# H19R1_Frontend_1.net
KiCad netlist of a schematic drawn in Altium Designer
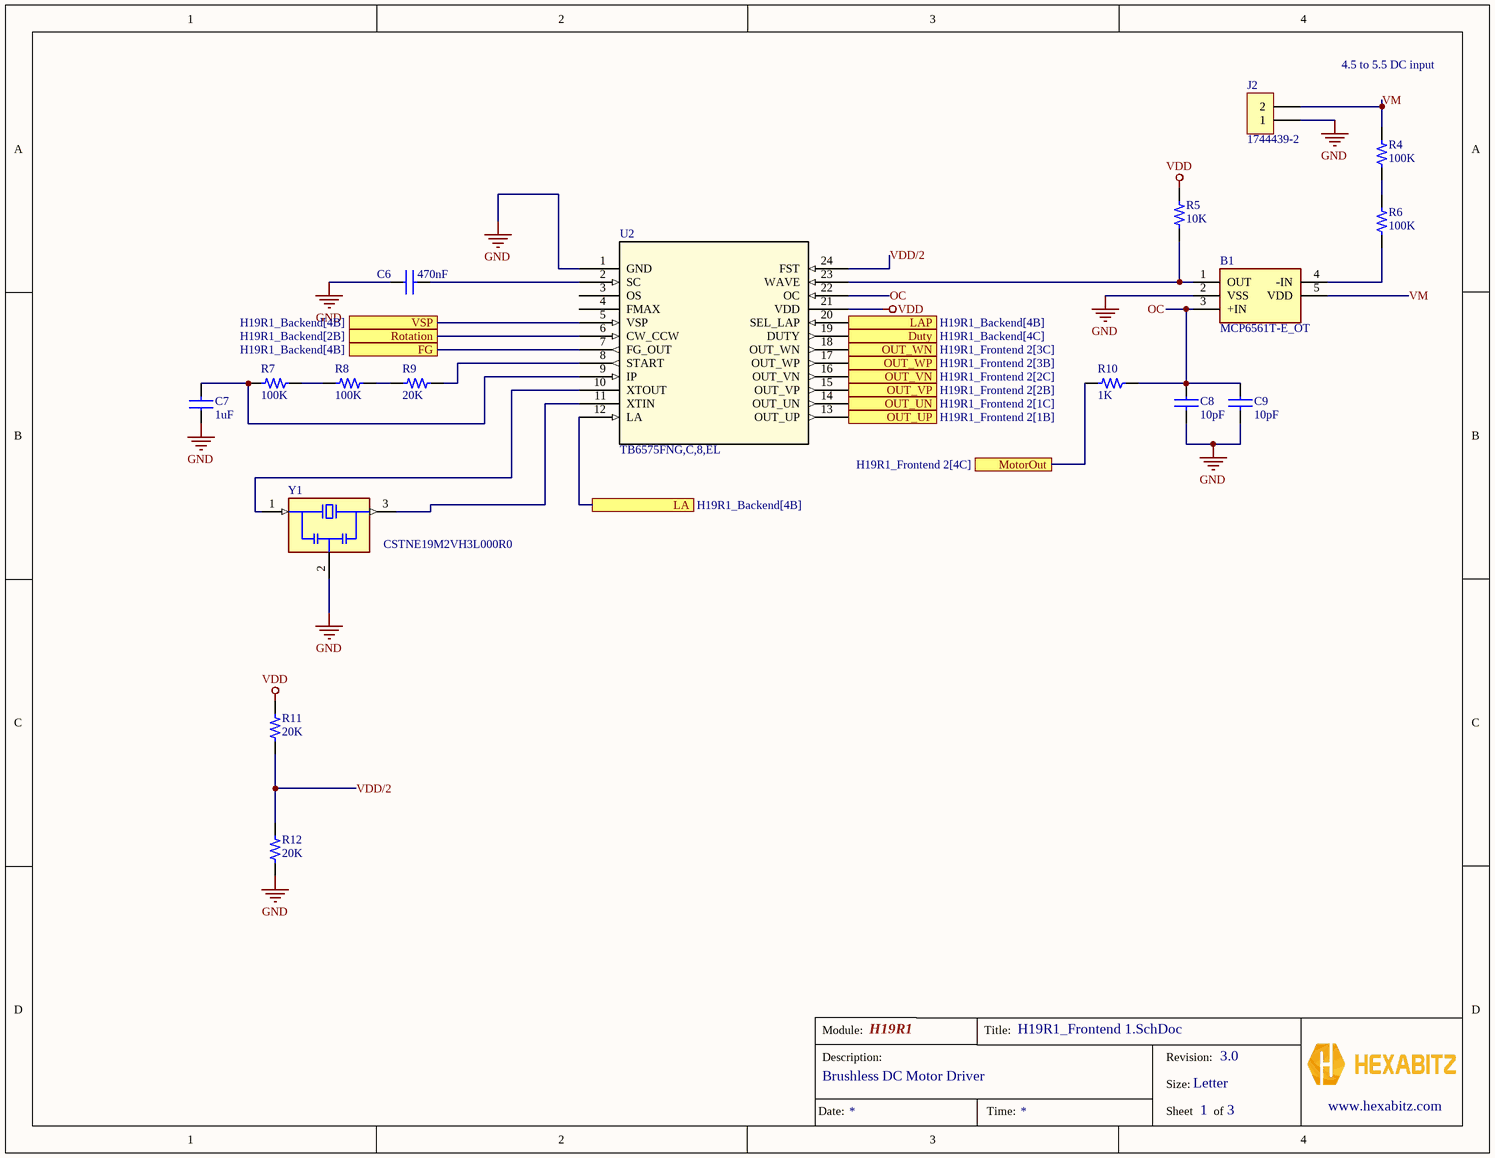
[diagram p0: H19R1_Frontend 1.SchDoc]

(export (version "E")
  (design (tool "Eeschema 10.0.6"))
  (components
    (comp (ref "B1")
      (value "MCP6561T-E_OT")
      (footprint "SOT95P270X145-5N")
      (description "Single 1.8V Push/Pull Comparator, E temp")
      (fields (field (name "MANUFACTURER_PART_NUMBER") "MCP6561T-E/OT"))
      (libsource (lib "MCP6561T-E_OT") (part "MCP6561T-E_OT"))
    )
    (comp (ref "C6")
      (value "470nF")
      (footprint "C0402")
      (description "Multilayer Ceramic Capacitor, 0.47 uF, 16 V, ± 10%, X7S, 0402 [1005 Metric]")
      (fields
        (field (name "MANUFACTURER") "TDK")
        (field (name "MANUFACTURER PART NUMBER") "C1005X7S1C474K050BC")
      )
      (libsource (lib "Passive") (part "C1005X7S1C474K050BC"))
    )
    (comp (ref "C7")
      (value "1uF")
      (footprint "C0402")
      (description "Multilayer Ceramic Capacitor, 1 Uf, 25 V, ½ 10%, X5R, 0402 [1005 Metric]")
      (fields
        (field (name "MANUFACTURER") "Samsung")
        (field (name "MANUFACTURER PART NUMBER") "CL05A105KA5NQNC")
      )
      (libsource (lib "Passive") (part "CL05A105KA5NQNC"))
    )
    (comp (ref "C8")
      (value "10pF")
      (footprint "C0402")
      (description "0402 10 pF 50 V ±5 % Tolerance NP0 SMT Multilayer Ceramic Capacitor")
      (fields
        (field (name "MANUFACTURER") "Yageo")
        (field (name "MANUFACTURER PART NUMBER") "CC0402JRNPO9BN100")
      )
      (libsource (lib "Passive") (part "CC0402JRNPO9BN100"))
    )
    (comp (ref "C9")
      (value "10pF")
      (footprint "C0402")
      (description "0402 10 pF 50 V ±5 % Tolerance NP0 SMT Multilayer Ceramic Capacitor")
      (fields
        (field (name "MANUFACTURER") "Yageo")
        (field (name "MANUFACTURER PART NUMBER") "CC0402JRNPO9BN100")
      )
      (libsource (lib "Passive") (part "CC0402JRNPO9BN100"))
    )
    (comp (ref "J2")
      (value "1744439-2")
      (footprint "17444392")
      (description "Conn Shrouded Header HDR 2 POS 2.5mm Crimp ST Cable Mount Bag/Box")
      (fields
        (field (name "MANUFACTURER") "TE Connectivity AMP")
        (field (name "MANUFACTURER PART NUMBER") "1744439-2")
      )
      (libsource (lib "Connectors") (part "1744439-2"))
    )
    (comp (ref "R4")
      (value "100K")
      (footprint "R0402_3")
      (description "Res Thick Film 0402 100K Ohm 1% 1/10W ±100ppm/°C Molded SMD Punched Carrier T/R")
      (fields
        (field (name "MANUFACTURER") "Panasonic")
        (field (name "MANUFACTURER PART NUMBER") "ERJ-2RKF1003X")
      )
      (libsource (lib "") (part "ERJ-2RKF1003X_1"))
    )
    (comp (ref "R5")
      (value "10K")
      (footprint "R0402_3")
      (description "SMD Chip Resistor, 10 Kohm, ½ 1%, 62.5 Mw, 0402 [1005 Metric], Thick Film, General Purpose")
      (fields
        (field (name "MANUFACTURER") "Yageo")
        (field (name "MANUFACTURER PART NUMBER") "RC0402FR-0710KL")
      )
      (libsource (lib "Passive") (part "RC0402FR-0710KL"))
    )
    (comp (ref "R6")
      (value "100K")
      (footprint "R0402_3")
      (description "Res Thick Film 0402 100K Ohm 1% 1/10W ±100ppm/°C Molded SMD Punched Carrier T/R")
      (fields
        (field (name "MANUFACTURER") "Panasonic")
        (field (name "MANUFACTURER PART NUMBER") "ERJ-2RKF1003X")
      )
      (libsource (lib "") (part "ERJ-2RKF1003X_1"))
    )
    (comp (ref "R7")
      (value "100K")
      (footprint "R0402_3")
      (description "Res Thick Film 0402 100K Ohm 1% 1/10W ±100ppm/°C Molded SMD Punched Carrier T/R")
      (fields
        (field (name "MANUFACTURER") "Panasonic")
        (field (name "MANUFACTURER PART NUMBER") "ERJ-2RKF1003X")
      )
      (libsource (lib "Passive") (part "ERJ-2RKF1003X"))
    )
    (comp (ref "R8")
      (value "100K")
      (footprint "R0402_3")
      (description "Res Thick Film 0402 100K Ohm 1% 1/10W ±100ppm/°C Molded SMD Punched Carrier T/R")
      (fields
        (field (name "MANUFACTURER") "Panasonic")
        (field (name "MANUFACTURER PART NUMBER") "ERJ-2RKF1003X")
      )
      (libsource (lib "Passive") (part "ERJ-2RKF1003X"))
    )
    (comp (ref "R9")
      (value "20K")
      (footprint "R0402_3")
      (description "Res Thick Film 0402 20K Ohm 1% 0.063W(1/16W) ±100ppm/C Pad SMD Automotive T/R")
      (fields
        (field (name "MANUFACTURER") "Stackpole Electronics")
        (field (name "MANUFACTURER PART NUMBER") "RMCF0402FT20K0")
      )
      (libsource (lib "") (part "RMCF0402FT20K0_1"))
    )
    (comp (ref "R10")
      (value "1K")
      (footprint "R0402_3")
      (description "SMD Chip Resistor 1 Kohm ½ 1% 62.5 Mw 0402 [1005 Metric] Thick Film General Purpose")
      (fields
        (field (name "MANUFACTURER") "Yageo")
        (field (name "MANUFACTURER PART NUMBER") "RC0402FR-071KL")
      )
      (libsource (lib "Passive") (part "RC0402FR-071KL"))
    )
    (comp (ref "R11")
      (value "20K")
      (footprint "R0402_3")
      (description "Res Thick Film 0402 20K Ohm 1% 0.063W(1/16W) ±100ppm/C Pad SMD Automotive T/R")
      (fields
        (field (name "MANUFACTURER") "Stackpole Electronics")
        (field (name "MANUFACTURER PART NUMBER") "RMCF0402FT20K0")
      )
      (libsource (lib "Passive") (part "RMCF0402FT20K0"))
    )
    (comp (ref "R12")
      (value "20K")
      (footprint "R0402_3")
      (description "Res Thick Film 0402 20K Ohm 1% 0.063W(1/16W) ±100ppm/C Pad SMD Automotive T/R")
      (fields
        (field (name "MANUFACTURER") "Stackpole Electronics")
        (field (name "MANUFACTURER PART NUMBER") "RMCF0402FT20K0")
      )
      (libsource (lib "Passive") (part "RMCF0402FT20K0"))
    )
    (comp (ref "U2")
      (value "TB6575FNG,C,8,EL")
      (footprint "SSOP24-P-300-0p65A_TOS")
      (description "No Description Available")
      (fields (field (name "COPYRIGHT") "Copyright (C) 2025 Ultra Librarian. All rights reserved."))
      (libsource (lib "TB6575FNG,C,8,EL") (part "TB6575FNG,C,8,EL"))
    )
    (comp (ref "Y1")
      (value "CSTNE19M2VH3L000R0")
      (footprint "OSC_CSTNE19M2VH3L000R0")
      (description "19.2MHz Ceramic Resonator Built in Capacitor 15pF Â±0.11% -40Â°C ~ 85Â°C Surface Mount")
      (fields (field (name "DIGI-KEY_PART_NUMBER") "490-18268-2-ND") (field (name "MF") "Murata Electronics"))
      (libsource (lib "CSTNE19M2VH3L000R0") (part "CSTNE19M2VH3L000R0"))
    )
  )
  (nets
    (net (code "1") (name "/Duty") (class "Default")
      (node (ref "U2") (pin "19") (pinfunction "DUTY_19") (pintype "output"))
    )
    (net (code "2") (name "/FG") (class "Default")
      (node (ref "U2") (pin "7") (pinfunction "FG_OUT_7") (pintype "output"))
    )
    (net (code "3") (name "/LA") (class "Default")
      (node (ref "U2") (pin "12") (pinfunction "LA_12") (pintype "input"))
    )
    (net (code "4") (name "/LAP") (class "Default")
      (node (ref "U2") (pin "20") (pinfunction "SEL_LAP_20") (pintype "input"))
    )
    (net (code "5") (name "/MotorOut") (class "Default")
      (node (ref "R10") (pin "1") (pinfunction "1_1") (pintype "passive"))
    )
    (net (code "6") (name "/OC") (class "Default")
      (node (ref "B1") (pin "3") (pinfunction "+IN_3") (pintype "passive"))
      (node (ref "C8") (pin "1") (pinfunction "1_1") (pintype "passive"))
      (node (ref "C9") (pin "1") (pinfunction "1_1") (pintype "passive"))
      (node (ref "R10") (pin "2") (pinfunction "2_2") (pintype "passive"))
      (node (ref "U2") (pin "22") (pinfunction "OC_22") (pintype "input"))
    )
    (net (code "7") (name "/OUT_UN") (class "Default")
      (node (ref "U2") (pin "14") (pinfunction "OUT_UN_14") (pintype "output"))
    )
    (net (code "8") (name "/OUT_UP") (class "Default")
      (node (ref "U2") (pin "13") (pinfunction "OUT_UP_13") (pintype "output"))
    )
    (net (code "9") (name "/OUT_VN") (class "Default")
      (node (ref "U2") (pin "16") (pinfunction "OUT_VN_16") (pintype "output"))
    )
    (net (code "10") (name "/OUT_VP") (class "Default")
      (node (ref "U2") (pin "15") (pinfunction "OUT_VP_15") (pintype "output"))
    )
    (net (code "11") (name "/OUT_WN") (class "Default")
      (node (ref "U2") (pin "18") (pinfunction "OUT_WN_18") (pintype "output"))
    )
    (net (code "12") (name "/OUT_WP") (class "Default")
      (node (ref "U2") (pin "17") (pinfunction "OUT_WP_17") (pintype "output"))
    )
    (net (code "13") (name "/Rotation") (class "Default")
      (node (ref "U2") (pin "6") (pinfunction "CW_CCW_6") (pintype "input"))
    )
    (net (code "14") (name "/VDD{slash}2") (class "Default")
      (node (ref "R11") (pin "2") (pinfunction "2_2") (pintype "passive"))
      (node (ref "R12") (pin "1") (pinfunction "1_1") (pintype "passive"))
      (node (ref "U2") (pin "24") (pinfunction "FST_24") (pintype "input"))
    )
    (net (code "15") (name "/VM") (class "Default")
      (node (ref "B1") (pin "5") (pinfunction "VDD_5") (pintype "passive"))
      (node (ref "J2") (pin "2") (pinfunction "2_2") (pintype "passive"))
      (node (ref "R4") (pin "2") (pinfunction "2_2") (pintype "passive"))
    )
    (net (code "16") (name "/VSP") (class "Default")
      (node (ref "U2") (pin "5") (pinfunction "VSP_5") (pintype "input"))
    )
    (net (code "17") (name "GND") (class "Default")
      (node (ref "B1") (pin "2") (pinfunction "VSS_2") (pintype "passive"))
      (node (ref "C6") (pin "1") (pinfunction "1_1") (pintype "passive"))
      (node (ref "C7") (pin "1") (pinfunction "1_1") (pintype "passive"))
      (node (ref "C8") (pin "2") (pinfunction "2_2") (pintype "passive"))
      (node (ref "C9") (pin "2") (pinfunction "2_2") (pintype "passive"))
      (node (ref "J2") (pin "1") (pinfunction "1_1") (pintype "passive"))
      (node (ref "R12") (pin "2") (pinfunction "2_2") (pintype "passive"))
      (node (ref "U2") (pin "1") (pinfunction "GND_1") (pintype "power_in"))
      (node (ref "Y1") (pin "2") (pinfunction "GND_2") (pintype "power_in"))
    )
    (net (code "18") (name "Net-(B1--IN)") (class "Default")
      (node (ref "B1") (pin "4") (pinfunction "-IN_4") (pintype "passive"))
      (node (ref "R6") (pin "1") (pinfunction "1_1") (pintype "passive"))
    )
    (net (code "19") (name "Net-(B1-OUT)") (class "Default")
      (node (ref "B1") (pin "1") (pinfunction "OUT_1") (pintype "passive"))
      (node (ref "R5") (pin "1") (pinfunction "1_1") (pintype "passive"))
      (node (ref "U2") (pin "23") (pinfunction "WAVE_23") (pintype "input"))
    )
    (net (code "20") (name "Net-(R4-Pad1)") (class "Default")
      (node (ref "R4") (pin "1") (pinfunction "1_1") (pintype "passive"))
      (node (ref "R6") (pin "2") (pinfunction "2_2") (pintype "passive"))
    )
    (net (code "21") (name "Net-(R7-Pad2)") (class "Default")
      (node (ref "R7") (pin "2") (pinfunction "2_2") (pintype "passive"))
      (node (ref "R8") (pin "1") (pinfunction "1_1") (pintype "passive"))
    )
    (net (code "22") (name "Net-(R8-Pad2)") (class "Default")
      (node (ref "R8") (pin "2") (pinfunction "2_2") (pintype "passive"))
      (node (ref "R9") (pin "2") (pinfunction "2_2") (pintype "passive"))
    )
    (net (code "23") (name "Net-(U2-IP)") (class "Default")
      (node (ref "C7") (pin "2") (pinfunction "2_2") (pintype "passive"))
      (node (ref "R7") (pin "1") (pinfunction "1_1") (pintype "passive"))
      (node (ref "U2") (pin "9") (pinfunction "IP_9") (pintype "input"))
    )
    (net (code "24") (name "Net-(U2-SC)") (class "Default")
      (node (ref "C6") (pin "2") (pinfunction "2_2") (pintype "passive"))
      (node (ref "U2") (pin "2") (pinfunction "SC_2") (pintype "input"))
    )
    (net (code "25") (name "Net-(U2-START)") (class "Default")
      (node (ref "R9") (pin "1") (pinfunction "1_1") (pintype "passive"))
      (node (ref "U2") (pin "8") (pinfunction "START_8") (pintype "output"))
    )
    (net (code "26") (name "Net-(U2-XTIN)") (class "Default")
      (node (ref "U2") (pin "11") (pinfunction "XTIN_11") (pintype "passive"))
      (node (ref "Y1") (pin "3") (pinfunction "OUT_3") (pintype "output"))
    )
    (net (code "27") (name "Net-(U2-XTOUT)") (class "Default")
      (node (ref "U2") (pin "10") (pinfunction "XTOUT_10") (pintype "passive"))
      (node (ref "Y1") (pin "1") (pinfunction "IN_1") (pintype "input"))
    )
    (net (code "28") (name "VDD") (class "Default")
      (node (ref "R11") (pin "1") (pinfunction "1_1") (pintype "passive"))
      (node (ref "R5") (pin "2") (pinfunction "2_2") (pintype "passive"))
      (node (ref "U2") (pin "21") (pinfunction "VDD_21") (pintype "power_in"))
    )
    (net (code "29") (name "unconnected-(U2-FMAX-Pad4)") (class "Default")
      (node (ref "U2") (pin "4") (pinfunction "FMAX_4") (pintype "passive"))
    )
    (net (code "30") (name "unconnected-(U2-OS-Pad3)") (class "Default")
      (node (ref "U2") (pin "3") (pinfunction "OS_3") (pintype "passive"))
    )
  )
)
